# clk.net
KiCad netlist of a schematic drawn in EAGLE
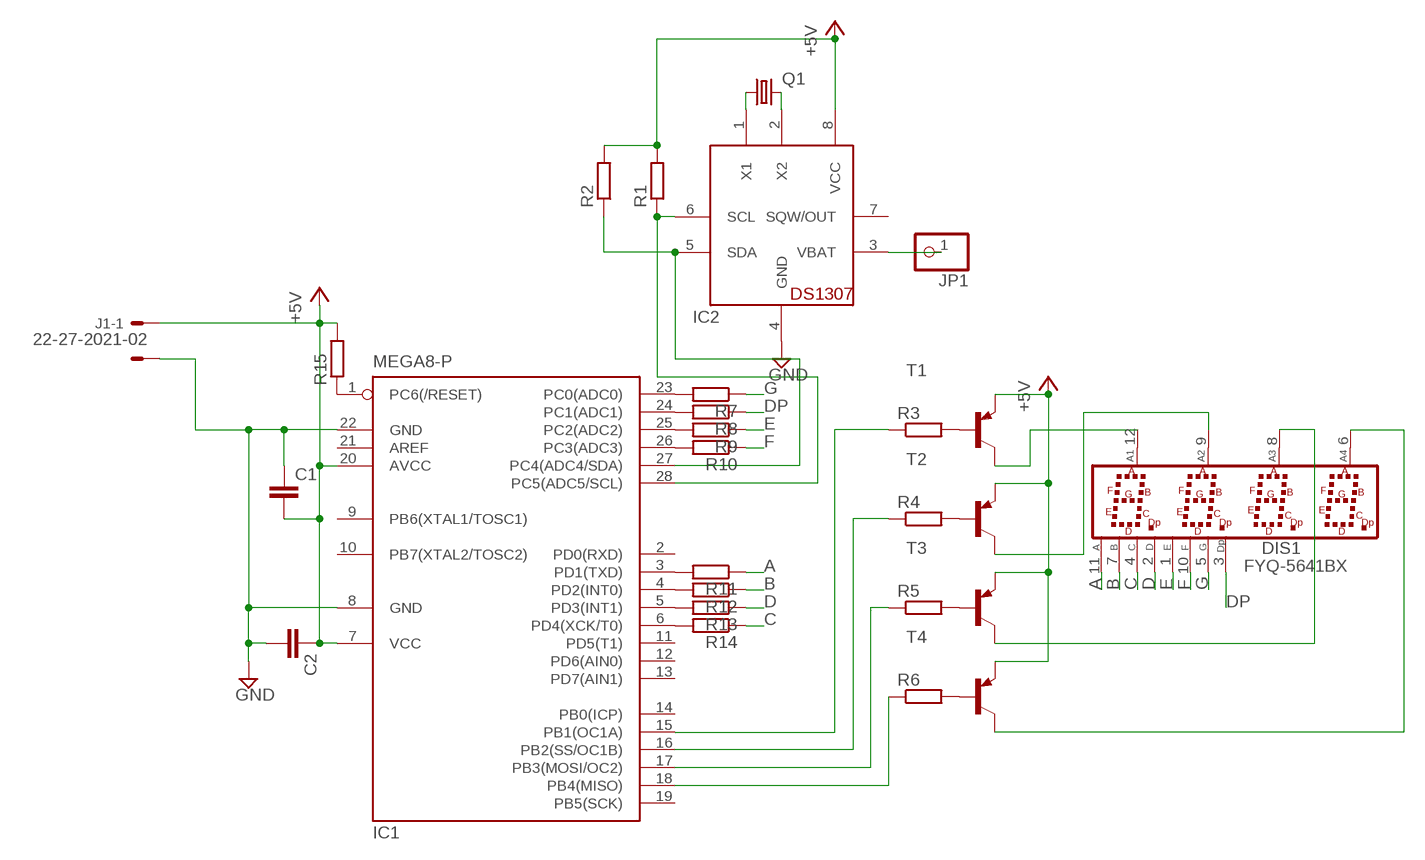
[diagram p0: schematic, sheet 1]

(export (version "E")
  (design (tool "Eeschema 10.0.6"))
  (components
    (comp (ref "C1")
      (value "C-EU025-024X044")
      (footprint "eagle-import:C025-024X044")
      (libsource (lib "eagle-import") (part "C-EU025-024X044"))
    )
    (comp (ref "C2")
      (value "C-EU025-024X044")
      (footprint "eagle-import:C025-024X044")
      (libsource (lib "eagle-import") (part "C-EU025-024X044"))
    )
    (comp (ref "DIS1")
      (value "FYQ-5641BX")
      (footprint "eagle-import:FYQ5641")
      (libsource (lib "eagle-import") (part "FYQ-5641BX"))
    )
    (comp (ref "IC1")
      (value "MEGA8-P")
      (footprint "eagle-import:DIL28-3")
      (libsource (lib "eagle-import") (part "MEGA8-P"))
    )
    (comp (ref "IC2")
      (value "DS1307")
      (footprint "eagle-import:DIL08")
      (libsource (lib "eagle-import") (part "DS1307"))
    )
    (comp (ref "J1")
      (value "22-27-2021-02")
      (footprint "eagle-import:6410-02")
      (libsource (lib "eagle-import") (part "22-?-0227-2021"))
    )
    (comp (ref "JP1")
      (value "PINHD-1X1")
      (footprint "eagle-import:1X01")
      (libsource (lib "eagle-import") (part "PINHD-1X1"))
    )
    (comp (ref "Q1")
      (value "CRYSTALTC26V")
      (footprint "eagle-import:TC26V")
      (libsource (lib "eagle-import") (part "CRYSTALTC26V"))
    )
    (comp (ref "R1")
      (value "R-EU_0207/2V")
      (footprint "eagle-import:0207_2V")
      (libsource (lib "eagle-import") (part "R-EU_0207/2V"))
    )
    (comp (ref "R2")
      (value "R-EU_0207/2V")
      (footprint "eagle-import:0207_2V")
      (libsource (lib "eagle-import") (part "R-EU_0207/2V"))
    )
    (comp (ref "R3")
      (value "R-EU_0204/2V")
      (footprint "eagle-import:0204V")
      (libsource (lib "eagle-import") (part "R-EU_0204/2V"))
    )
    (comp (ref "R4")
      (value "R-EU_0204/2V")
      (footprint "eagle-import:0204V")
      (libsource (lib "eagle-import") (part "R-EU_0204/2V"))
    )
    (comp (ref "R5")
      (value "R-EU_0204/2V")
      (footprint "eagle-import:0204V")
      (libsource (lib "eagle-import") (part "R-EU_0204/2V"))
    )
    (comp (ref "R6")
      (value "R-EU_0204/2V")
      (footprint "eagle-import:0204V")
      (libsource (lib "eagle-import") (part "R-EU_0204/2V"))
    )
    (comp (ref "R7")
      (value "R-EU_0207/2V")
      (footprint "eagle-import:0207_2V")
      (libsource (lib "eagle-import") (part "R-EU_0207/2V"))
    )
    (comp (ref "R8")
      (value "R-EU_0207/2V")
      (footprint "eagle-import:0207_2V")
      (libsource (lib "eagle-import") (part "R-EU_0207/2V"))
    )
    (comp (ref "R9")
      (value "R-EU_0207/2V")
      (footprint "eagle-import:0207_2V")
      (libsource (lib "eagle-import") (part "R-EU_0207/2V"))
    )
    (comp (ref "R10")
      (value "R-EU_0207/2V")
      (footprint "eagle-import:0207_2V")
      (libsource (lib "eagle-import") (part "R-EU_0207/2V"))
    )
    (comp (ref "R11")
      (value "R-EU_0207/2V")
      (footprint "eagle-import:0207_2V")
      (libsource (lib "eagle-import") (part "R-EU_0207/2V"))
    )
    (comp (ref "R12")
      (value "R-EU_0207/2V")
      (footprint "eagle-import:0207_2V")
      (libsource (lib "eagle-import") (part "R-EU_0207/2V"))
    )
    (comp (ref "R13")
      (value "R-EU_0207/2V")
      (footprint "eagle-import:0207_2V")
      (libsource (lib "eagle-import") (part "R-EU_0207/2V"))
    )
    (comp (ref "R14")
      (value "R-EU_0207/2V")
      (footprint "eagle-import:0207_2V")
      (libsource (lib "eagle-import") (part "R-EU_0207/2V"))
    )
    (comp (ref "R15")
      (value "R-EU_0204/2V")
      (footprint "eagle-import:0204V")
      (libsource (lib "eagle-import") (part "R-EU_0204/2V"))
    )
    (comp (ref "T1")
      (value "BC327-PNP-TO92-EBC")
      (footprint "eagle-import:TO92-EBC")
      (libsource (lib "eagle-import") (part "-PNP-TO92-EBCBC327"))
    )
    (comp (ref "T2")
      (value "BC327-PNP-TO92-EBC")
      (footprint "eagle-import:TO92-EBC")
      (libsource (lib "eagle-import") (part "-PNP-TO92-EBCBC327"))
    )
    (comp (ref "T3")
      (value "BC327-PNP-TO92-EBC")
      (footprint "eagle-import:TO92-EBC")
      (libsource (lib "eagle-import") (part "-PNP-TO92-EBCBC327"))
    )
    (comp (ref "T4")
      (value "BC327-PNP-TO92-EBC")
      (footprint "eagle-import:TO92-EBC")
      (libsource (lib "eagle-import") (part "-PNP-TO92-EBCBC327"))
    )
  )
  (nets
    (net (code "1") (name "+5V") (class "Default")
      (node (ref "C1") (pin "2") (pinfunction "2_2") (pintype "passive"))
      (node (ref "C2") (pin "1") (pinfunction "1_1") (pintype "passive"))
      (node (ref "IC1") (pin "20") (pinfunction "AVCC_20") (pintype "power_in"))
      (node (ref "IC1") (pin "7") (pinfunction "VCC_7") (pintype "power_in"))
      (node (ref "IC2") (pin "8") (pinfunction "VCC_8") (pintype "power_in"))
      (node (ref "J1") (pin "1") (pinfunction "S_1") (pintype "passive"))
      (node (ref "R1") (pin "2") (pinfunction "2_2") (pintype "passive"))
      (node (ref "R15") (pin "2") (pinfunction "2_2") (pintype "passive"))
      (node (ref "R2") (pin "2") (pinfunction "2_2") (pintype "passive"))
      (node (ref "T1") (pin "E") (pinfunction "E_E") (pintype "passive"))
      (node (ref "T2") (pin "E") (pinfunction "E_E") (pintype "passive"))
      (node (ref "T3") (pin "E") (pinfunction "E_E") (pintype "passive"))
      (node (ref "T4") (pin "E") (pinfunction "E_E") (pintype "passive"))
    )
    (net (code "2") (name "/A") (class "Default")
      (node (ref "DIS1") (pin "11") (pinfunction "A_11") (pintype "passive"))
      (node (ref "R11") (pin "1") (pinfunction "1_1") (pintype "passive"))
    )
    (net (code "3") (name "/B") (class "Default")
      (node (ref "DIS1") (pin "7") (pinfunction "B_7") (pintype "passive"))
      (node (ref "R12") (pin "1") (pinfunction "1_1") (pintype "passive"))
    )
    (net (code "4") (name "/C") (class "Default")
      (node (ref "DIS1") (pin "4") (pinfunction "C_4") (pintype "passive"))
      (node (ref "R14") (pin "1") (pinfunction "1_1") (pintype "passive"))
    )
    (net (code "5") (name "/D") (class "Default")
      (node (ref "DIS1") (pin "2") (pinfunction "D_2") (pintype "passive"))
      (node (ref "R13") (pin "1") (pinfunction "1_1") (pintype "passive"))
    )
    (net (code "6") (name "/DP") (class "Default")
      (node (ref "DIS1") (pin "3") (pinfunction "DP_3") (pintype "passive"))
      (node (ref "R8") (pin "1") (pinfunction "1_1") (pintype "passive"))
    )
    (net (code "7") (name "/E") (class "Default")
      (node (ref "DIS1") (pin "1") (pinfunction "E_1") (pintype "passive"))
      (node (ref "R9") (pin "1") (pinfunction "1_1") (pintype "passive"))
    )
    (net (code "8") (name "/F") (class "Default")
      (node (ref "DIS1") (pin "10") (pinfunction "F_10") (pintype "passive"))
      (node (ref "R10") (pin "1") (pinfunction "1_1") (pintype "passive"))
    )
    (net (code "9") (name "/G") (class "Default")
      (node (ref "DIS1") (pin "5") (pinfunction "G_5") (pintype "passive"))
      (node (ref "R7") (pin "1") (pinfunction "1_1") (pintype "passive"))
    )
    (net (code "10") (name "GND") (class "Default")
      (node (ref "C1") (pin "1") (pinfunction "1_1") (pintype "passive"))
      (node (ref "C2") (pin "2") (pinfunction "2_2") (pintype "passive"))
      (node (ref "IC1") (pin "22") (pinfunction "GND_22") (pintype "power_in"))
      (node (ref "IC1") (pin "8") (pinfunction "GND_8") (pintype "power_in"))
      (node (ref "IC2") (pin "4") (pinfunction "GND_4") (pintype "power_in"))
      (node (ref "J1") (pin "2") (pinfunction "S_2") (pintype "passive"))
    )
    (net (code "11") (name "Net-(DIS1-A1)") (class "Default")
      (node (ref "DIS1") (pin "12") (pinfunction "A1_12") (pintype "passive"))
      (node (ref "T1") (pin "C") (pinfunction "C_C") (pintype "passive"))
    )
    (net (code "12") (name "Net-(DIS1-A2)") (class "Default")
      (node (ref "DIS1") (pin "9") (pinfunction "A2_9") (pintype "passive"))
      (node (ref "T2") (pin "C") (pinfunction "C_C") (pintype "passive"))
    )
    (net (code "13") (name "Net-(DIS1-A3)") (class "Default")
      (node (ref "DIS1") (pin "8") (pinfunction "A3_8") (pintype "passive"))
      (node (ref "T3") (pin "C") (pinfunction "C_C") (pintype "passive"))
    )
    (net (code "14") (name "Net-(DIS1-A4)") (class "Default")
      (node (ref "DIS1") (pin "6") (pinfunction "A4_6") (pintype "passive"))
      (node (ref "T4") (pin "C") (pinfunction "C_C") (pintype "passive"))
    )
    (net (code "15") (name "Net-(IC1-PB1(OC1A))") (class "Default")
      (node (ref "IC1") (pin "15") (pinfunction "PB1(OC1A)_15") (pintype "bidirectional"))
      (node (ref "R3") (pin "1") (pinfunction "1_1") (pintype "passive"))
    )
    (net (code "16") (name "Net-(IC1-PB2(SS{slash}OC1B))") (class "Default")
      (node (ref "IC1") (pin "16") (pinfunction "PB2(SS/OC1B)_16") (pintype "bidirectional"))
      (node (ref "R4") (pin "1") (pinfunction "1_1") (pintype "passive"))
    )
    (net (code "17") (name "Net-(IC1-PB3(MOSI{slash}OC2))") (class "Default")
      (node (ref "IC1") (pin "17") (pinfunction "PB3(MOSI/OC2)_17") (pintype "bidirectional"))
      (node (ref "R5") (pin "1") (pinfunction "1_1") (pintype "passive"))
    )
    (net (code "18") (name "Net-(IC1-PB4(MISO))") (class "Default")
      (node (ref "IC1") (pin "18") (pinfunction "PB4(MISO)_18") (pintype "bidirectional"))
      (node (ref "R6") (pin "1") (pinfunction "1_1") (pintype "passive"))
    )
    (net (code "19") (name "Net-(IC1-PC0(ADC0))") (class "Default")
      (node (ref "IC1") (pin "23") (pinfunction "PC0(ADC0)_23") (pintype "bidirectional"))
      (node (ref "R7") (pin "2") (pinfunction "2_2") (pintype "passive"))
    )
    (net (code "20") (name "Net-(IC1-PC1(ADC1))") (class "Default")
      (node (ref "IC1") (pin "24") (pinfunction "PC1(ADC1)_24") (pintype "bidirectional"))
      (node (ref "R8") (pin "2") (pinfunction "2_2") (pintype "passive"))
    )
    (net (code "21") (name "Net-(IC1-PC2(ADC2))") (class "Default")
      (node (ref "IC1") (pin "25") (pinfunction "PC2(ADC2)_25") (pintype "bidirectional"))
      (node (ref "R9") (pin "2") (pinfunction "2_2") (pintype "passive"))
    )
    (net (code "22") (name "Net-(IC1-PC3(ADC3))") (class "Default")
      (node (ref "IC1") (pin "26") (pinfunction "PC3(ADC3)_26") (pintype "bidirectional"))
      (node (ref "R10") (pin "2") (pinfunction "2_2") (pintype "passive"))
    )
    (net (code "23") (name "Net-(IC1-PC4(ADC4{slash}SDA))") (class "Default")
      (node (ref "IC1") (pin "27") (pinfunction "PC4(ADC4/SDA)_27") (pintype "bidirectional"))
      (node (ref "IC2") (pin "5") (pinfunction "SDA_5") (pintype "bidirectional"))
      (node (ref "R2") (pin "1") (pinfunction "1_1") (pintype "passive"))
    )
    (net (code "24") (name "Net-(IC1-PC5(ADC5{slash}SCL))") (class "Default")
      (node (ref "IC1") (pin "28") (pinfunction "PC5(ADC5/SCL)_28") (pintype "bidirectional"))
      (node (ref "IC2") (pin "6") (pinfunction "SCL_6") (pintype "bidirectional"))
      (node (ref "R1") (pin "1") (pinfunction "1_1") (pintype "passive"))
    )
    (net (code "25") (name "Net-(IC1-PC6({slash}RESET))") (class "Default")
      (node (ref "IC1") (pin "1") (pinfunction "PC6(/RESET)_1") (pintype "bidirectional"))
      (node (ref "R15") (pin "1") (pinfunction "1_1") (pintype "passive"))
    )
    (net (code "26") (name "Net-(IC1-PD1(TXD))") (class "Default")
      (node (ref "IC1") (pin "3") (pinfunction "PD1(TXD)_3") (pintype "bidirectional"))
      (node (ref "R11") (pin "2") (pinfunction "2_2") (pintype "passive"))
    )
    (net (code "27") (name "Net-(IC1-PD2(INT0))") (class "Default")
      (node (ref "IC1") (pin "4") (pinfunction "PD2(INT0)_4") (pintype "bidirectional"))
      (node (ref "R12") (pin "2") (pinfunction "2_2") (pintype "passive"))
    )
    (net (code "28") (name "Net-(IC1-PD3(INT1))") (class "Default")
      (node (ref "IC1") (pin "5") (pinfunction "PD3(INT1)_5") (pintype "bidirectional"))
      (node (ref "R13") (pin "2") (pinfunction "2_2") (pintype "passive"))
    )
    (net (code "29") (name "Net-(IC1-PD4(XCK{slash}T0))") (class "Default")
      (node (ref "IC1") (pin "6") (pinfunction "PD4(XCK/T0)_6") (pintype "bidirectional"))
      (node (ref "R14") (pin "2") (pinfunction "2_2") (pintype "passive"))
    )
    (net (code "30") (name "Net-(IC2-VBAT)") (class "Default")
      (node (ref "IC2") (pin "3") (pinfunction "VBAT_3") (pintype "power_in"))
      (node (ref "JP1") (pin "1") (pinfunction "1_1") (pintype "passive"))
    )
    (net (code "31") (name "Net-(IC2-X1)") (class "Default")
      (node (ref "IC2") (pin "1") (pinfunction "X1_1") (pintype "passive"))
      (node (ref "Q1") (pin "1") (pinfunction "1_1") (pintype "passive"))
    )
    (net (code "32") (name "Net-(IC2-X2)") (class "Default")
      (node (ref "IC2") (pin "2") (pinfunction "X2_2") (pintype "passive"))
      (node (ref "Q1") (pin "2") (pinfunction "2_2") (pintype "passive"))
    )
    (net (code "33") (name "Net-(R3-Pad2)") (class "Default")
      (node (ref "R3") (pin "2") (pinfunction "2_2") (pintype "passive"))
      (node (ref "T1") (pin "B") (pinfunction "B_B") (pintype "passive"))
    )
    (net (code "34") (name "Net-(R4-Pad2)") (class "Default")
      (node (ref "R4") (pin "2") (pinfunction "2_2") (pintype "passive"))
      (node (ref "T2") (pin "B") (pinfunction "B_B") (pintype "passive"))
    )
    (net (code "35") (name "Net-(R5-Pad2)") (class "Default")
      (node (ref "R5") (pin "2") (pinfunction "2_2") (pintype "passive"))
      (node (ref "T3") (pin "B") (pinfunction "B_B") (pintype "passive"))
    )
    (net (code "36") (name "Net-(R6-Pad2)") (class "Default")
      (node (ref "R6") (pin "2") (pinfunction "2_2") (pintype "passive"))
      (node (ref "T4") (pin "B") (pinfunction "B_B") (pintype "passive"))
    )
    (net (code "37") (name "unconnected-(IC1-AREF-Pad21)") (class "Default")
      (node (ref "IC1") (pin "21") (pinfunction "AREF_21") (pintype "passive"))
    )
    (net (code "38") (name "unconnected-(IC1-PB0(ICP)-Pad14)") (class "Default")
      (node (ref "IC1") (pin "14") (pinfunction "PB0(ICP)_14") (pintype "bidirectional"))
    )
    (net (code "39") (name "unconnected-(IC1-PB5(SCK)-Pad19)") (class "Default")
      (node (ref "IC1") (pin "19") (pinfunction "PB5(SCK)_19") (pintype "bidirectional"))
    )
    (net (code "40") (name "unconnected-(IC1-PB6(XTAL1{slash}TOSC1)-Pad9)") (class "Default")
      (node (ref "IC1") (pin "9") (pinfunction "PB6(XTAL1/TOSC1)_9") (pintype "bidirectional"))
    )
    (net (code "41") (name "unconnected-(IC1-PB7(XTAL2{slash}TOSC2)-Pad10)") (class "Default")
      (node (ref "IC1") (pin "10") (pinfunction "PB7(XTAL2/TOSC2)_10") (pintype "bidirectional"))
    )
    (net (code "42") (name "unconnected-(IC1-PD0(RXD)-Pad2)") (class "Default")
      (node (ref "IC1") (pin "2") (pinfunction "PD0(RXD)_2") (pintype "bidirectional"))
    )
    (net (code "43") (name "unconnected-(IC1-PD5(T1)-Pad11)") (class "Default")
      (node (ref "IC1") (pin "11") (pinfunction "PD5(T1)_11") (pintype "bidirectional"))
    )
    (net (code "44") (name "unconnected-(IC1-PD6(AIN0)-Pad12)") (class "Default")
      (node (ref "IC1") (pin "12") (pinfunction "PD6(AIN0)_12") (pintype "bidirectional"))
    )
    (net (code "45") (name "unconnected-(IC1-PD7(AIN1)-Pad13)") (class "Default")
      (node (ref "IC1") (pin "13") (pinfunction "PD7(AIN1)_13") (pintype "bidirectional"))
    )
    (net (code "46") (name "unconnected-(IC2-SQW{slash}OUT-Pad7)") (class "Default")
      (node (ref "IC2") (pin "7") (pinfunction "SQW/OUT_7") (pintype "bidirectional"))
    )
  )
)
